# strain-gauge-amplifer-v1.net
KiCad netlist of a schematic drawn in EAGLE
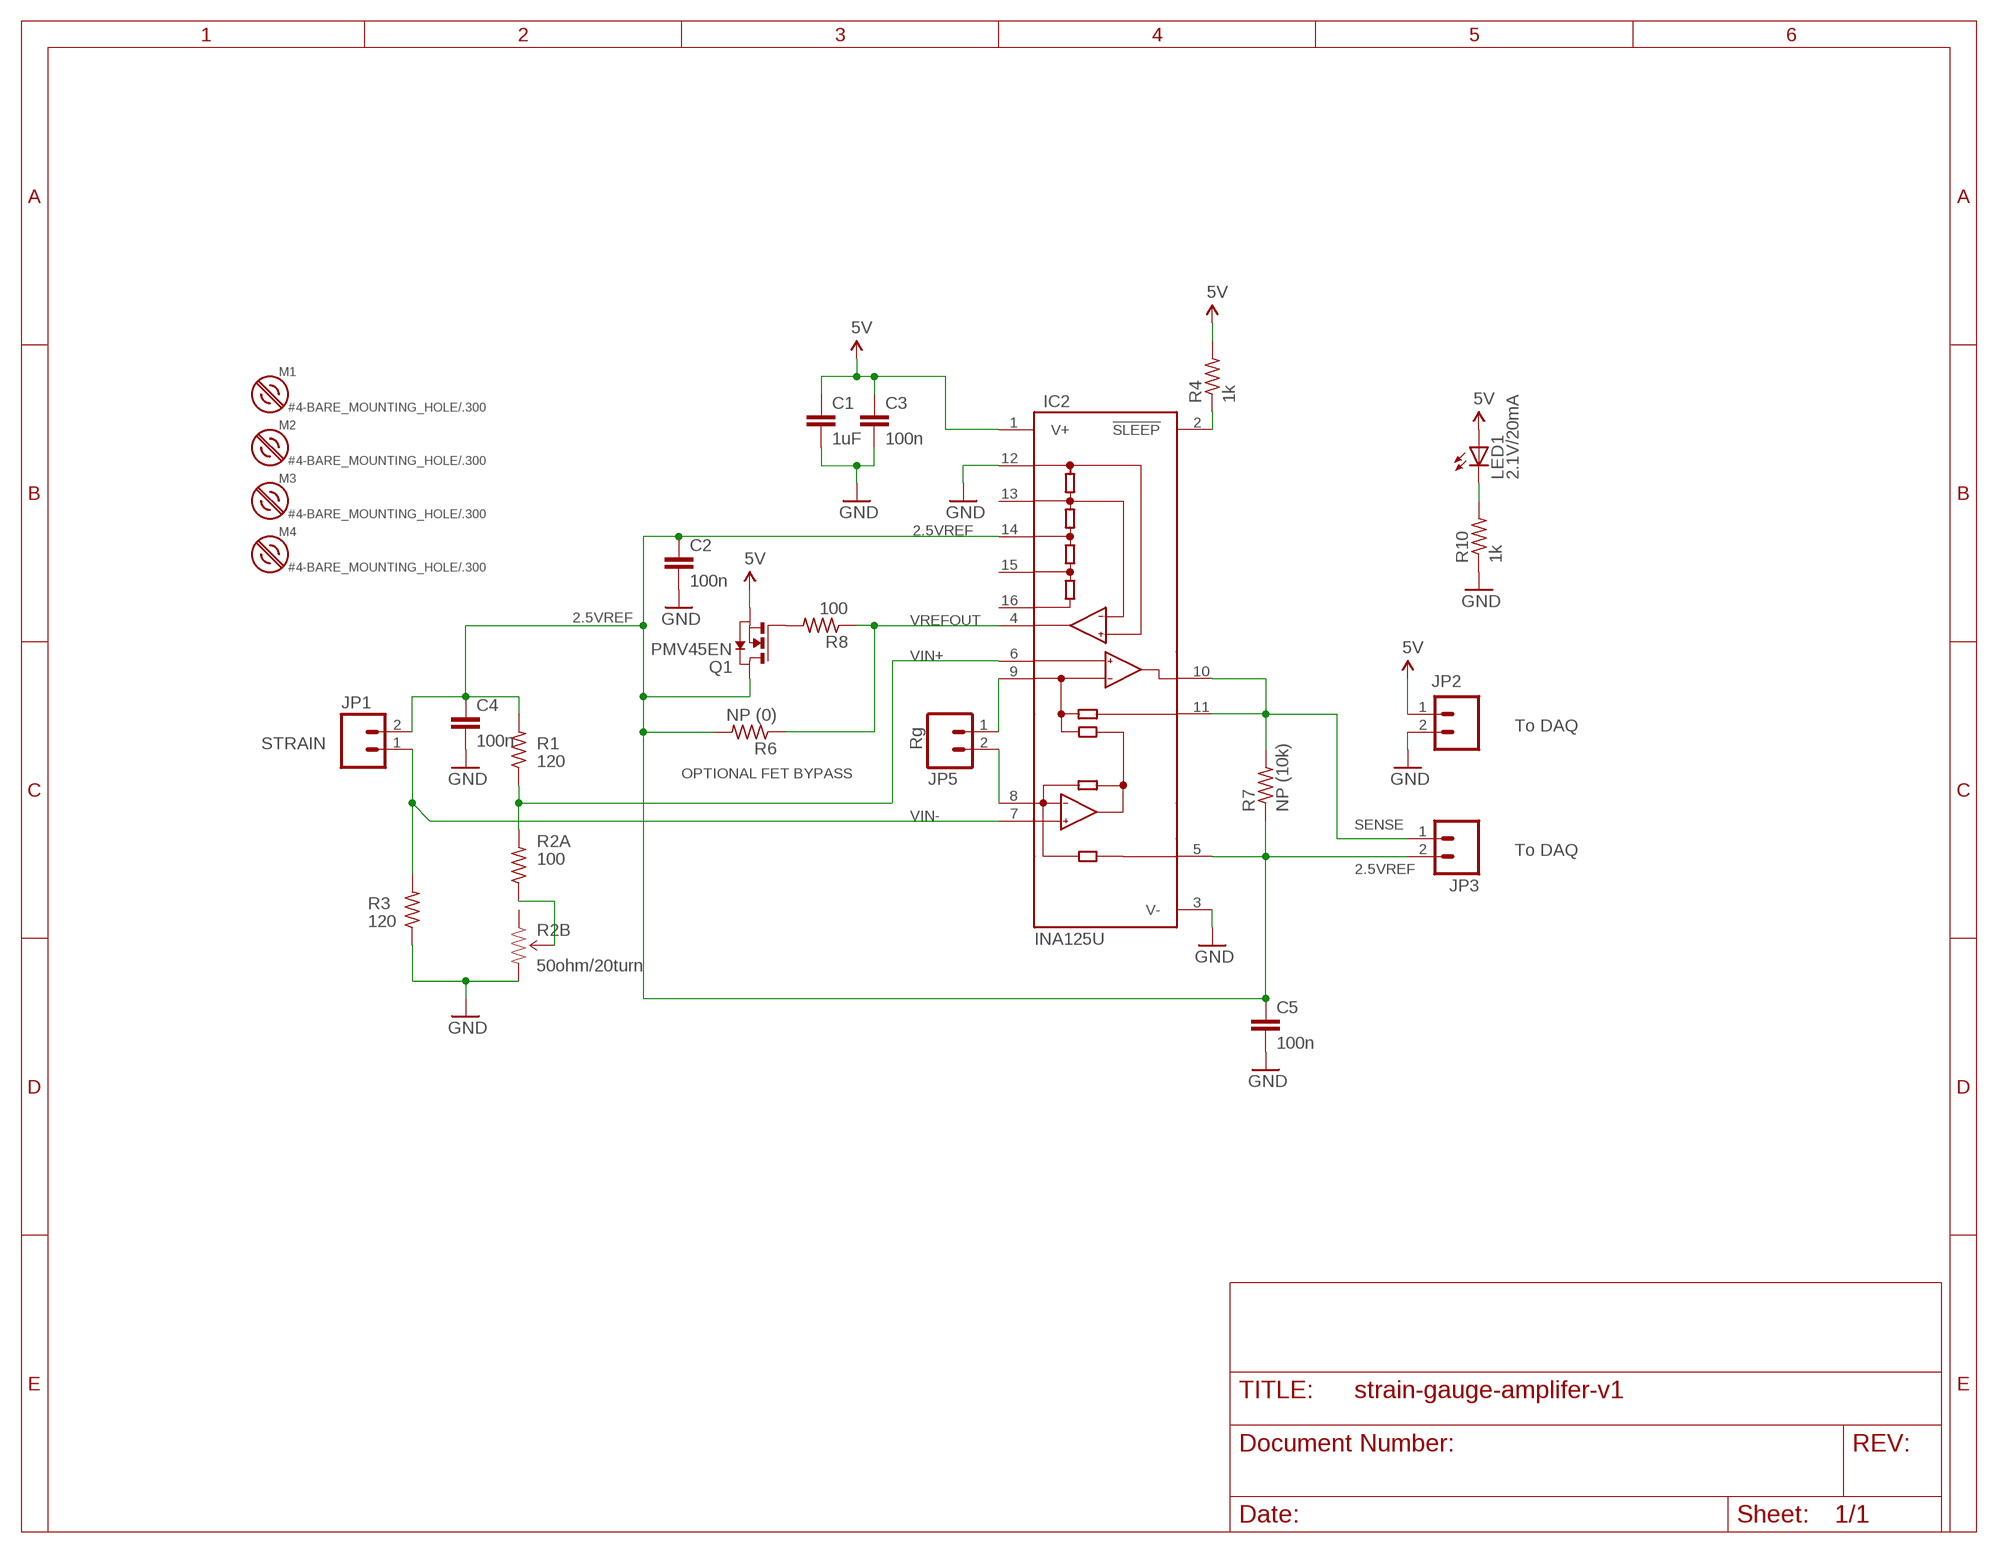
[diagram p0: schematic, sheet 1]

(export (version "E")
  (design (tool "Eeschema 10.0.6"))
  (components
    (comp (ref "C1")
      (value "1uF")
      (footprint "eagle-import:0805-C-NOSILK")
      (libsource (lib "eagle-import") (part "C-EU0805-C-NOSILK"))
    )
    (comp (ref "C2")
      (value "100n")
      (footprint "eagle-import:0805-C-NOSILK")
      (libsource (lib "eagle-import") (part "C-EU0805-C-NOSILK"))
    )
    (comp (ref "C3")
      (value "100n")
      (footprint "eagle-import:0805-C-NOSILK")
      (libsource (lib "eagle-import") (part "C-EU0805-C-NOSILK"))
    )
    (comp (ref "C4")
      (value "100n")
      (footprint "eagle-import:0805-C-NOSILK")
      (libsource (lib "eagle-import") (part "C-EU0805-C-NOSILK"))
    )
    (comp (ref "C5")
      (value "100n")
      (footprint "eagle-import:0805-C-NOSILK")
      (libsource (lib "eagle-import") (part "C-EU0805-C-NOSILK"))
    )
    (comp (ref "IC2")
      (value "INA125U")
      (footprint "eagle-import:SO16-1")
      (fields (field (name "MF") "TEXAS INSTRUMENT CONNECTORS"))
      (libsource (lib "eagle-import") (part "INA125U"))
    )
    (comp (ref "JP1")
      (value "STRAIN")
      (footprint "eagle-import:SCREWTERMINAL-5MM-2")
      (libsource (lib "eagle-import") (part "M025MM"))
    )
    (comp (ref "JP2")
      (value "M025MM")
      (footprint "eagle-import:SCREWTERMINAL-5MM-2")
      (libsource (lib "eagle-import") (part "M025MM"))
    )
    (comp (ref "JP3")
      (value "M025MM")
      (footprint "eagle-import:SCREWTERMINAL-5MM-2")
      (libsource (lib "eagle-import") (part "M025MM"))
    )
    (comp (ref "JP5")
      (value "Rg")
      (footprint "eagle-import:SCREWTERMINAL-5MM-2")
      (libsource (lib "eagle-import") (part "M025MM"))
    )
    (comp (ref "LED1")
      (value "2.1V/20mA")
      (footprint "eagle-import:LED-0603")
      (libsource (lib "eagle-import") (part "LED0603"))
    )
    (comp (ref "M1")
      (value "#4-BARE_MOUNTING_HOLE/.300")
      (footprint "eagle-import:#4_.300-BARE+STD_NUT_OR_STAR_WASHER")
      (libsource (lib "eagle-import") (part "#4-BARE_MOUNTING_HOLE/.300"))
    )
    (comp (ref "M2")
      (value "#4-BARE_MOUNTING_HOLE/.300")
      (footprint "eagle-import:#4_.300-BARE+STD_NUT_OR_STAR_WASHER")
      (libsource (lib "eagle-import") (part "#4-BARE_MOUNTING_HOLE/.300"))
    )
    (comp (ref "M3")
      (value "#4-BARE_MOUNTING_HOLE/.300")
      (footprint "eagle-import:#4_.300-BARE+STD_NUT_OR_STAR_WASHER")
      (libsource (lib "eagle-import") (part "#4-BARE_MOUNTING_HOLE/.300"))
    )
    (comp (ref "M4")
      (value "#4-BARE_MOUNTING_HOLE/.300")
      (footprint "eagle-import:#4_.300-BARE+STD_NUT_OR_STAR_WASHER")
      (libsource (lib "eagle-import") (part "#4-BARE_MOUNTING_HOLE/.300"))
    )
    (comp (ref "Q1")
      (value "PMV45EN")
      (footprint "eagle-import:SOT23")
      (libsource (lib "eagle-import") (part "PMV45EN"))
    )
    (comp (ref "R1")
      (value "120")
      (footprint "eagle-import:0805-C-NOSILK")
      (libsource (lib "eagle-import") (part "R-US_0805-C-NOSILK"))
    )
    (comp (ref "R2A")
      (value "100")
      (footprint "eagle-import:0805-C-NOSILK")
      (libsource (lib "eagle-import") (part "R-US_0805-C-NOSILK"))
    )
    (comp (ref "R2B")
      (value "50ohm/20turn")
      (footprint "eagle-import:TRIMPOT-5MM")
      (libsource (lib "eagle-import") (part "TRIMPOTTRIMPOT-5MM"))
    )
    (comp (ref "R3")
      (value "120")
      (footprint "eagle-import:0805-C-NOSILK")
      (libsource (lib "eagle-import") (part "R-US_0805-C-NOSILK"))
    )
    (comp (ref "R4")
      (value "1k")
      (footprint "eagle-import:0805-C-NOSILK")
      (libsource (lib "eagle-import") (part "R-US_0805-C-NOSILK"))
    )
    (comp (ref "R6")
      (value "NP (0)")
      (footprint "eagle-import:0805-C-NOSILK")
      (libsource (lib "eagle-import") (part "R-US_0805-C-NOSILK"))
    )
    (comp (ref "R7")
      (value "NP (10k)")
      (footprint "eagle-import:0805-C-NOSILK")
      (libsource (lib "eagle-import") (part "R-US_0805-C-NOSILK"))
    )
    (comp (ref "R8")
      (value "100")
      (footprint "eagle-import:0805-C-NOSILK")
      (libsource (lib "eagle-import") (part "R-US_0805-C-NOSILK"))
    )
    (comp (ref "R10")
      (value "1k")
      (footprint "eagle-import:0805-C-NOSILK")
      (libsource (lib "eagle-import") (part "R-US_0805-C-NOSILK"))
    )
  )
  (nets
    (net (code "1") (name "/2.5VREF") (class "Default")
      (node (ref "C2") (pin "1") (pinfunction "1_1") (pintype "passive"))
      (node (ref "C4") (pin "1") (pinfunction "1_1") (pintype "passive"))
      (node (ref "C5") (pin "1") (pinfunction "1_1") (pintype "passive"))
      (node (ref "IC2") (pin "14") (pinfunction "REF2.5_14") (pintype "output"))
      (node (ref "IC2") (pin "5") (pinfunction "REF_5") (pintype "passive"))
      (node (ref "JP1") (pin "2") (pinfunction "2_2") (pintype "passive"))
      (node (ref "JP3") (pin "2") (pinfunction "2_2") (pintype "passive"))
      (node (ref "Q1") (pin "3") (pinfunction "D_3") (pintype "passive"))
      (node (ref "R1") (pin "2") (pinfunction "2_2") (pintype "passive"))
      (node (ref "R6") (pin "2") (pinfunction "2_2") (pintype "passive"))
      (node (ref "R7") (pin "1") (pinfunction "1_1") (pintype "passive"))
    )
    (net (code "2") (name "/SENSE") (class "Default")
      (node (ref "IC2") (pin "10") (pinfunction "OUT_10") (pintype "output"))
      (node (ref "IC2") (pin "11") (pinfunction "SENSE_11") (pintype "passive"))
      (node (ref "JP3") (pin "1") (pinfunction "1_1") (pintype "passive"))
      (node (ref "R7") (pin "2") (pinfunction "2_2") (pintype "passive"))
    )
    (net (code "3") (name "/VIN+") (class "Default")
      (node (ref "IC2") (pin "6") (pinfunction "+IN_6") (pintype "input"))
      (node (ref "R1") (pin "1") (pinfunction "1_1") (pintype "passive"))
      (node (ref "R2A") (pin "2") (pinfunction "2_2") (pintype "passive"))
    )
    (net (code "4") (name "/VIN-") (class "Default")
      (node (ref "IC2") (pin "7") (pinfunction "-VIN_7") (pintype "input"))
      (node (ref "JP1") (pin "1") (pinfunction "1_1") (pintype "passive"))
      (node (ref "R3") (pin "2") (pinfunction "2_2") (pintype "passive"))
    )
    (net (code "5") (name "/VREFOUT") (class "Default")
      (node (ref "IC2") (pin "4") (pinfunction "REFOUT_4") (pintype "output"))
      (node (ref "R6") (pin "1") (pinfunction "1_1") (pintype "passive"))
      (node (ref "R8") (pin "1") (pinfunction "1_1") (pintype "passive"))
    )
    (net (code "6") (name "5V") (class "Default")
      (node (ref "C1") (pin "1") (pinfunction "1_1") (pintype "passive"))
      (node (ref "C3") (pin "1") (pinfunction "1_1") (pintype "passive"))
      (node (ref "IC2") (pin "1") (pinfunction "V+_1") (pintype "power_in"))
      (node (ref "JP2") (pin "1") (pinfunction "1_1") (pintype "passive"))
      (node (ref "LED1") (pin "A") (pinfunction "A_A") (pintype "passive"))
      (node (ref "Q1") (pin "2") (pinfunction "S_2") (pintype "passive"))
      (node (ref "R4") (pin "2") (pinfunction "2_2") (pintype "passive"))
    )
    (net (code "7") (name "GND") (class "Default")
      (node (ref "C1") (pin "2") (pinfunction "2_2") (pintype "passive"))
      (node (ref "C2") (pin "2") (pinfunction "2_2") (pintype "passive"))
      (node (ref "C3") (pin "2") (pinfunction "2_2") (pintype "passive"))
      (node (ref "C4") (pin "2") (pinfunction "2_2") (pintype "passive"))
      (node (ref "C5") (pin "2") (pinfunction "2_2") (pintype "passive"))
      (node (ref "IC2") (pin "12") (pinfunction "REFCOM_12") (pintype "passive"))
      (node (ref "IC2") (pin "3") (pinfunction "V-_3") (pintype "power_in"))
      (node (ref "JP2") (pin "2") (pinfunction "2_2") (pintype "passive"))
      (node (ref "R10") (pin "1") (pinfunction "1_1") (pintype "passive"))
      (node (ref "R2B") (pin "C") (pinfunction "CW_C") (pintype "passive"))
      (node (ref "R3") (pin "1") (pinfunction "1_1") (pintype "passive"))
    )
    (net (code "8") (name "Net-(IC2-RG-Pad8)") (class "Default")
      (node (ref "IC2") (pin "8") (pinfunction "RG_8") (pintype "passive"))
      (node (ref "JP5") (pin "2") (pinfunction "2_2") (pintype "passive"))
    )
    (net (code "9") (name "Net-(IC2-RG-Pad9)") (class "Default")
      (node (ref "IC2") (pin "9") (pinfunction "RG_9") (pintype "passive"))
      (node (ref "JP5") (pin "1") (pinfunction "1_1") (pintype "passive"))
    )
    (net (code "10") (name "Net-(IC2-~{SLEEP})") (class "Default")
      (node (ref "IC2") (pin "2") (pinfunction "~{SLEEP}_2") (pintype "input"))
      (node (ref "R4") (pin "1") (pinfunction "1_1") (pintype "passive"))
    )
    (net (code "11") (name "Net-(LED1-PadC)") (class "Default")
      (node (ref "LED1") (pin "C") (pinfunction "C_C") (pintype "passive"))
      (node (ref "R10") (pin "2") (pinfunction "2_2") (pintype "passive"))
    )
    (net (code "12") (name "Net-(Q1-G)") (class "Default")
      (node (ref "Q1") (pin "1") (pinfunction "G_1") (pintype "passive"))
      (node (ref "R8") (pin "2") (pinfunction "2_2") (pintype "passive"))
    )
    (net (code "13") (name "Net-(R2B-WIPER)") (class "Default")
      (node (ref "R2A") (pin "1") (pinfunction "1_1") (pintype "passive"))
      (node (ref "R2B") (pin "B") (pinfunction "WIPER_B") (pintype "passive"))
    )
    (net (code "14") (name "unconnected-(IC2-REF5-Pad15)") (class "Default")
      (node (ref "IC2") (pin "15") (pinfunction "REF5_15") (pintype "output"))
    )
    (net (code "15") (name "unconnected-(IC2-REF10-Pad16)") (class "Default")
      (node (ref "IC2") (pin "16") (pinfunction "REF10_16") (pintype "output"))
    )
    (net (code "16") (name "unconnected-(IC2-REFBG-Pad13)") (class "Default")
      (node (ref "IC2") (pin "13") (pinfunction "REFBG_13") (pintype "output"))
    )
    (net (code "17") (name "unconnected-(R2B-CCW-PadA)") (class "Default")
      (node (ref "R2B") (pin "A") (pinfunction "CCW_A") (pintype "passive"))
    )
  )
)
